# 8-Bit_Instruction_Register.net
KiCad netlist of a schematic drawn in EAGLE
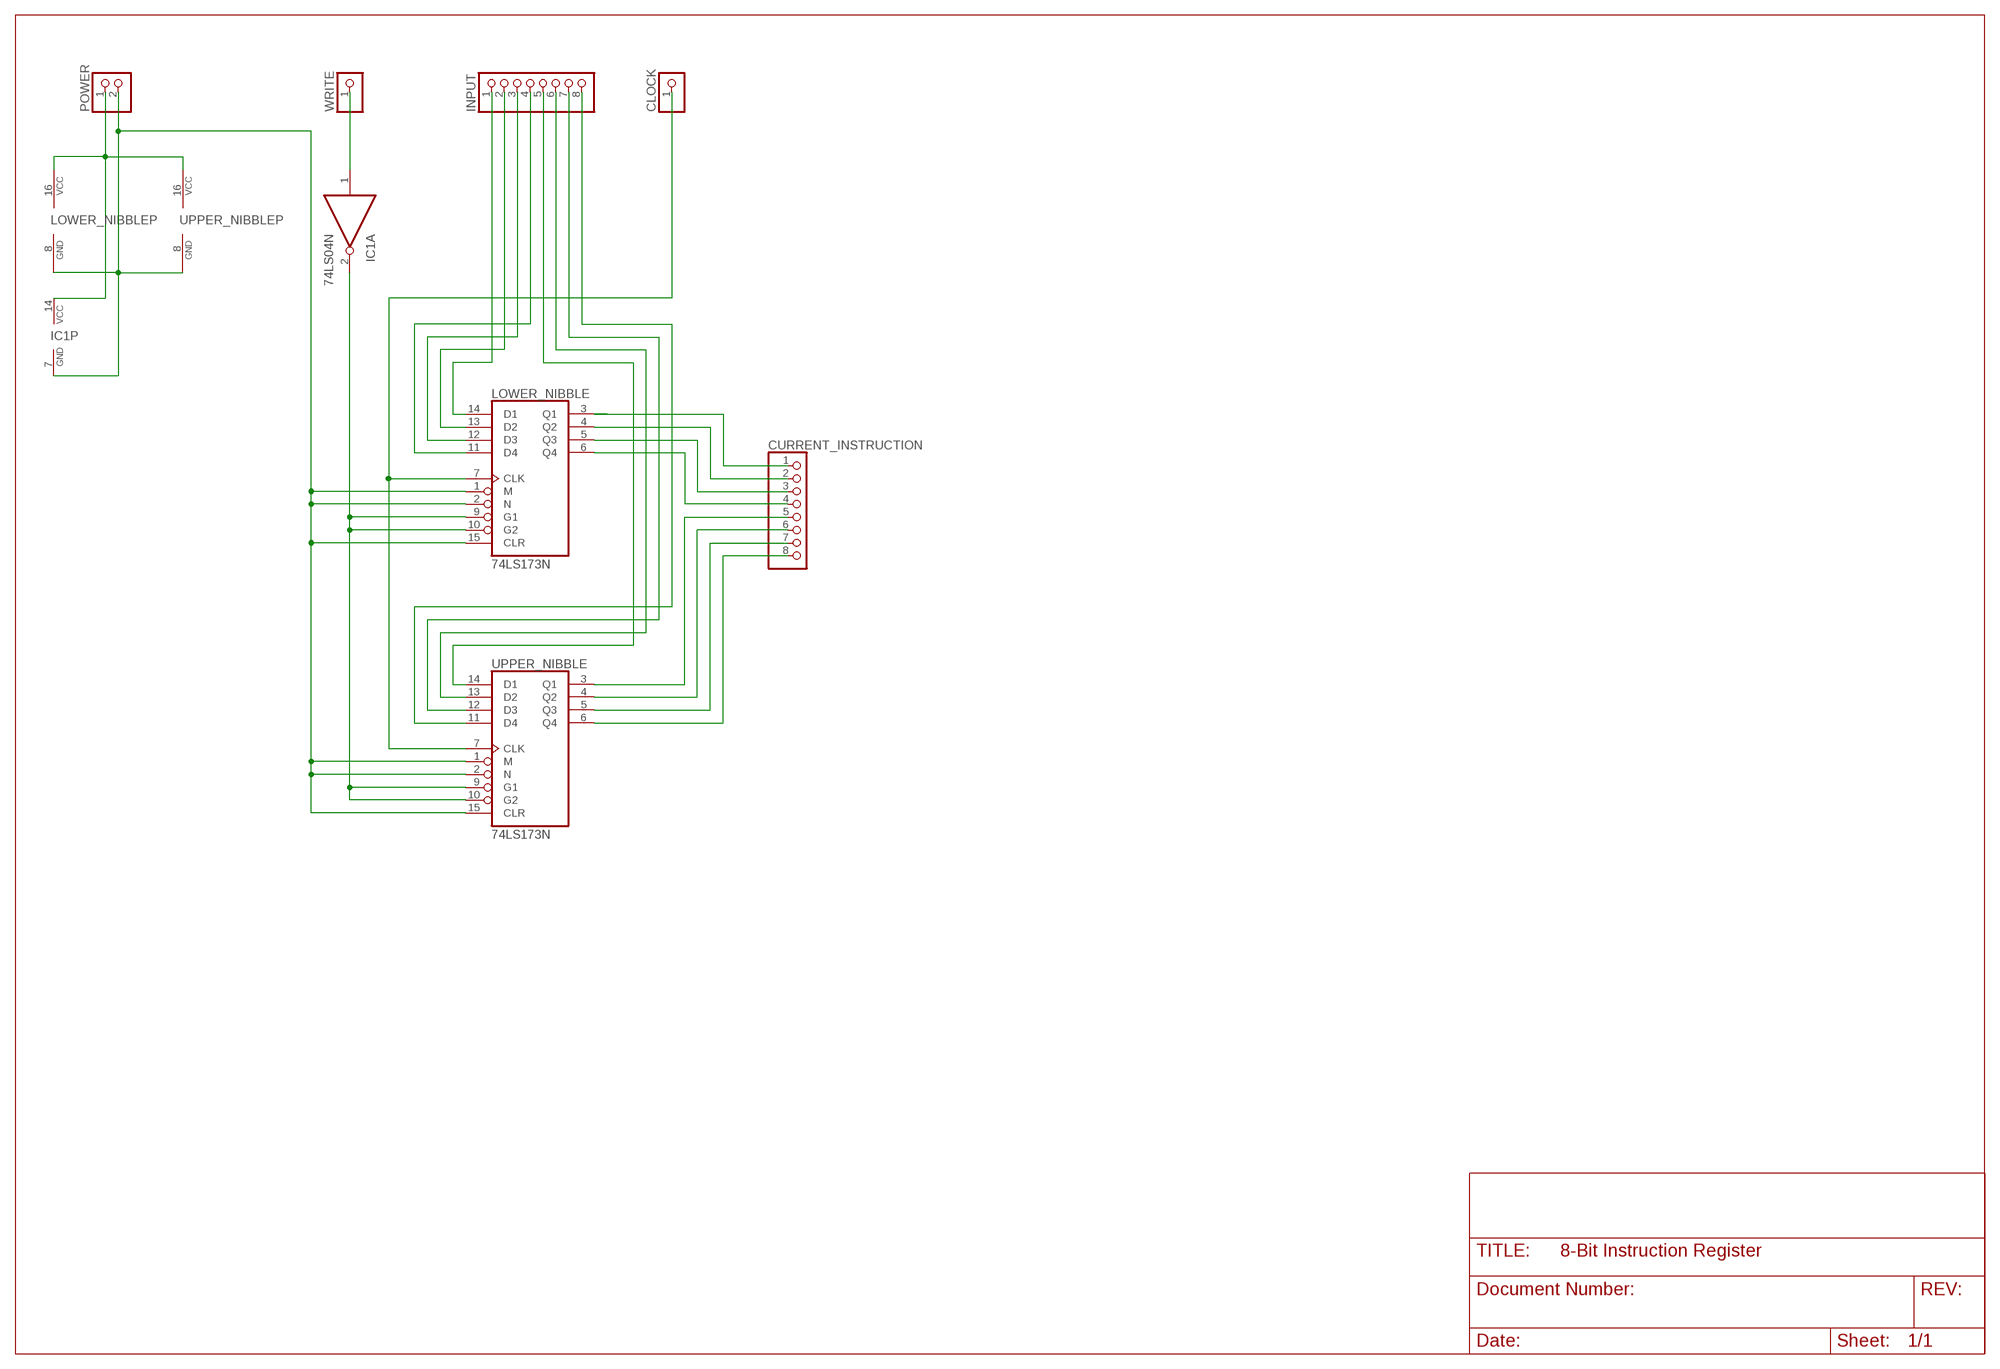
[diagram p0: schematic, sheet 1]

(export (version "E")
  (design (tool "Eeschema 10.0.6"))
  (components
    (comp (ref "CLOCK")
      (value "PINHD-1X1")
      (footprint "eagle-import:1X01")
      (libsource (lib "eagle-import") (part "PINHD-1X1"))
    )
    (comp (ref "CURRENT_INSTRUCTION")
      (value "PINHD-1X8")
      (footprint "eagle-import:1X08")
      (libsource (lib "eagle-import") (part "PINHD-1X8"))
    )
    (comp (ref "IC1")
      (value "74LS04N")
      (footprint "eagle-import:DIL14")
      (libsource (lib "eagle-import") (part "7404NLS"))
    )
    (comp (ref "INPUT")
      (value "PINHD-1X8")
      (footprint "eagle-import:1X08")
      (libsource (lib "eagle-import") (part "PINHD-1X8"))
    )
    (comp (ref "LOWER_NIBBLE")
      (value "74LS173N")
      (footprint "eagle-import:DIL16")
      (libsource (lib "eagle-import") (part "74173NLS"))
    )
    (comp (ref "POWER")
      (value "PINHD-1X2")
      (footprint "eagle-import:1X02")
      (libsource (lib "eagle-import") (part "PINHD-1X2"))
    )
    (comp (ref "UPPER_NIBBLE")
      (value "74LS173N")
      (footprint "eagle-import:DIL16")
      (libsource (lib "eagle-import") (part "74173NLS"))
    )
    (comp (ref "WRITE")
      (value "PINHD-1X1")
      (footprint "eagle-import:1X01")
      (libsource (lib "eagle-import") (part "PINHD-1X1"))
    )
  )
  (nets
    (net (code "1") (name "Net-(IC1A-I)") (class "Default")
      (node (ref "IC1") (pin "1") (pinfunction "I_1") (pintype "input"))
      (node (ref "WRITE") (pin "1") (pinfunction "1_1") (pintype "passive"))
    )
    (net (code "2") (name "Net-(IC1A-O)") (class "Default")
      (node (ref "IC1") (pin "2") (pinfunction "O_2") (pintype "output"))
      (node (ref "LOWER_NIBBLE") (pin "10") (pinfunction "G2_10") (pintype "input"))
      (node (ref "LOWER_NIBBLE") (pin "9") (pinfunction "G1_9") (pintype "input"))
      (node (ref "UPPER_NIBBLE") (pin "10") (pinfunction "G2_10") (pintype "input"))
      (node (ref "UPPER_NIBBLE") (pin "9") (pinfunction "G1_9") (pintype "input"))
    )
    (net (code "3") (name "Net-(IC1G-GND)") (class "Default")
      (node (ref "IC1") (pin "7") (pinfunction "GND_7") (pintype "power_in"))
      (node (ref "LOWER_NIBBLE") (pin "1") (pinfunction "M_1") (pintype "input"))
      (node (ref "LOWER_NIBBLE") (pin "15") (pinfunction "CLR_15") (pintype "input"))
      (node (ref "LOWER_NIBBLE") (pin "2") (pinfunction "N_2") (pintype "input"))
      (node (ref "LOWER_NIBBLE") (pin "8") (pinfunction "GND_8") (pintype "power_in"))
      (node (ref "POWER") (pin "2") (pinfunction "2_2") (pintype "passive"))
      (node (ref "UPPER_NIBBLE") (pin "1") (pinfunction "M_1") (pintype "input"))
      (node (ref "UPPER_NIBBLE") (pin "15") (pinfunction "CLR_15") (pintype "input"))
      (node (ref "UPPER_NIBBLE") (pin "2") (pinfunction "N_2") (pintype "input"))
      (node (ref "UPPER_NIBBLE") (pin "8") (pinfunction "GND_8") (pintype "power_in"))
    )
    (net (code "4") (name "Net-(IC1G-VCC)") (class "Default")
      (node (ref "IC1") (pin "14") (pinfunction "VCC_14") (pintype "power_in"))
      (node (ref "LOWER_NIBBLE") (pin "16") (pinfunction "VCC_16") (pintype "power_in"))
      (node (ref "POWER") (pin "1") (pinfunction "1_1") (pintype "passive"))
      (node (ref "UPPER_NIBBLE") (pin "16") (pinfunction "VCC_16") (pintype "power_in"))
    )
    (net (code "5") (name "Net-(LOWER_NIBBLEA-CLK)") (class "Default")
      (node (ref "CLOCK") (pin "1") (pinfunction "1_1") (pintype "passive"))
      (node (ref "LOWER_NIBBLE") (pin "7") (pinfunction "CLK_7") (pintype "input"))
      (node (ref "UPPER_NIBBLE") (pin "7") (pinfunction "CLK_7") (pintype "input"))
    )
    (net (code "6") (name "Net-(LOWER_NIBBLEA-D1)") (class "Default")
      (node (ref "INPUT") (pin "1") (pinfunction "1_1") (pintype "passive"))
      (node (ref "LOWER_NIBBLE") (pin "14") (pinfunction "D1_14") (pintype "input"))
    )
    (net (code "7") (name "Net-(LOWER_NIBBLEA-D2)") (class "Default")
      (node (ref "INPUT") (pin "2") (pinfunction "2_2") (pintype "passive"))
      (node (ref "LOWER_NIBBLE") (pin "13") (pinfunction "D2_13") (pintype "input"))
    )
    (net (code "8") (name "Net-(LOWER_NIBBLEA-D3)") (class "Default")
      (node (ref "INPUT") (pin "3") (pinfunction "3_3") (pintype "passive"))
      (node (ref "LOWER_NIBBLE") (pin "12") (pinfunction "D3_12") (pintype "input"))
    )
    (net (code "9") (name "Net-(LOWER_NIBBLEA-D4)") (class "Default")
      (node (ref "INPUT") (pin "4") (pinfunction "4_4") (pintype "passive"))
      (node (ref "LOWER_NIBBLE") (pin "11") (pinfunction "D4_11") (pintype "input"))
    )
    (net (code "10") (name "Net-(LOWER_NIBBLEA-Q1)") (class "Default")
      (node (ref "CURRENT_INSTRUCTION") (pin "1") (pinfunction "1_1") (pintype "passive"))
      (node (ref "LOWER_NIBBLE") (pin "3") (pinfunction "Q1_3") (pintype "tri_state"))
    )
    (net (code "11") (name "Net-(LOWER_NIBBLEA-Q2)") (class "Default")
      (node (ref "CURRENT_INSTRUCTION") (pin "2") (pinfunction "2_2") (pintype "passive"))
      (node (ref "LOWER_NIBBLE") (pin "4") (pinfunction "Q2_4") (pintype "tri_state"))
    )
    (net (code "12") (name "Net-(LOWER_NIBBLEA-Q3)") (class "Default")
      (node (ref "CURRENT_INSTRUCTION") (pin "3") (pinfunction "3_3") (pintype "passive"))
      (node (ref "LOWER_NIBBLE") (pin "5") (pinfunction "Q3_5") (pintype "tri_state"))
    )
    (net (code "13") (name "Net-(LOWER_NIBBLEA-Q4)") (class "Default")
      (node (ref "CURRENT_INSTRUCTION") (pin "4") (pinfunction "4_4") (pintype "passive"))
      (node (ref "LOWER_NIBBLE") (pin "6") (pinfunction "Q4_6") (pintype "tri_state"))
    )
    (net (code "14") (name "Net-(UPPER_NIBBLEA-D1)") (class "Default")
      (node (ref "INPUT") (pin "5") (pinfunction "5_5") (pintype "passive"))
      (node (ref "UPPER_NIBBLE") (pin "14") (pinfunction "D1_14") (pintype "input"))
    )
    (net (code "15") (name "Net-(UPPER_NIBBLEA-D2)") (class "Default")
      (node (ref "INPUT") (pin "6") (pinfunction "6_6") (pintype "passive"))
      (node (ref "UPPER_NIBBLE") (pin "13") (pinfunction "D2_13") (pintype "input"))
    )
    (net (code "16") (name "Net-(UPPER_NIBBLEA-D3)") (class "Default")
      (node (ref "INPUT") (pin "7") (pinfunction "7_7") (pintype "passive"))
      (node (ref "UPPER_NIBBLE") (pin "12") (pinfunction "D3_12") (pintype "input"))
    )
    (net (code "17") (name "Net-(UPPER_NIBBLEA-D4)") (class "Default")
      (node (ref "INPUT") (pin "8") (pinfunction "8_8") (pintype "passive"))
      (node (ref "UPPER_NIBBLE") (pin "11") (pinfunction "D4_11") (pintype "input"))
    )
    (net (code "18") (name "Net-(UPPER_NIBBLEA-Q1)") (class "Default")
      (node (ref "CURRENT_INSTRUCTION") (pin "5") (pinfunction "5_5") (pintype "passive"))
      (node (ref "UPPER_NIBBLE") (pin "3") (pinfunction "Q1_3") (pintype "tri_state"))
    )
    (net (code "19") (name "Net-(UPPER_NIBBLEA-Q2)") (class "Default")
      (node (ref "CURRENT_INSTRUCTION") (pin "6") (pinfunction "6_6") (pintype "passive"))
      (node (ref "UPPER_NIBBLE") (pin "4") (pinfunction "Q2_4") (pintype "tri_state"))
    )
    (net (code "20") (name "Net-(UPPER_NIBBLEA-Q3)") (class "Default")
      (node (ref "CURRENT_INSTRUCTION") (pin "7") (pinfunction "7_7") (pintype "passive"))
      (node (ref "UPPER_NIBBLE") (pin "5") (pinfunction "Q3_5") (pintype "tri_state"))
    )
    (net (code "21") (name "Net-(UPPER_NIBBLEA-Q4)") (class "Default")
      (node (ref "CURRENT_INSTRUCTION") (pin "8") (pinfunction "8_8") (pintype "passive"))
      (node (ref "UPPER_NIBBLE") (pin "6") (pinfunction "Q4_6") (pintype "tri_state"))
    )
  )
)
